# RasPi-BplusHAT_CamSlot.net
KiCad netlist of a schematic drawn in EAGLE
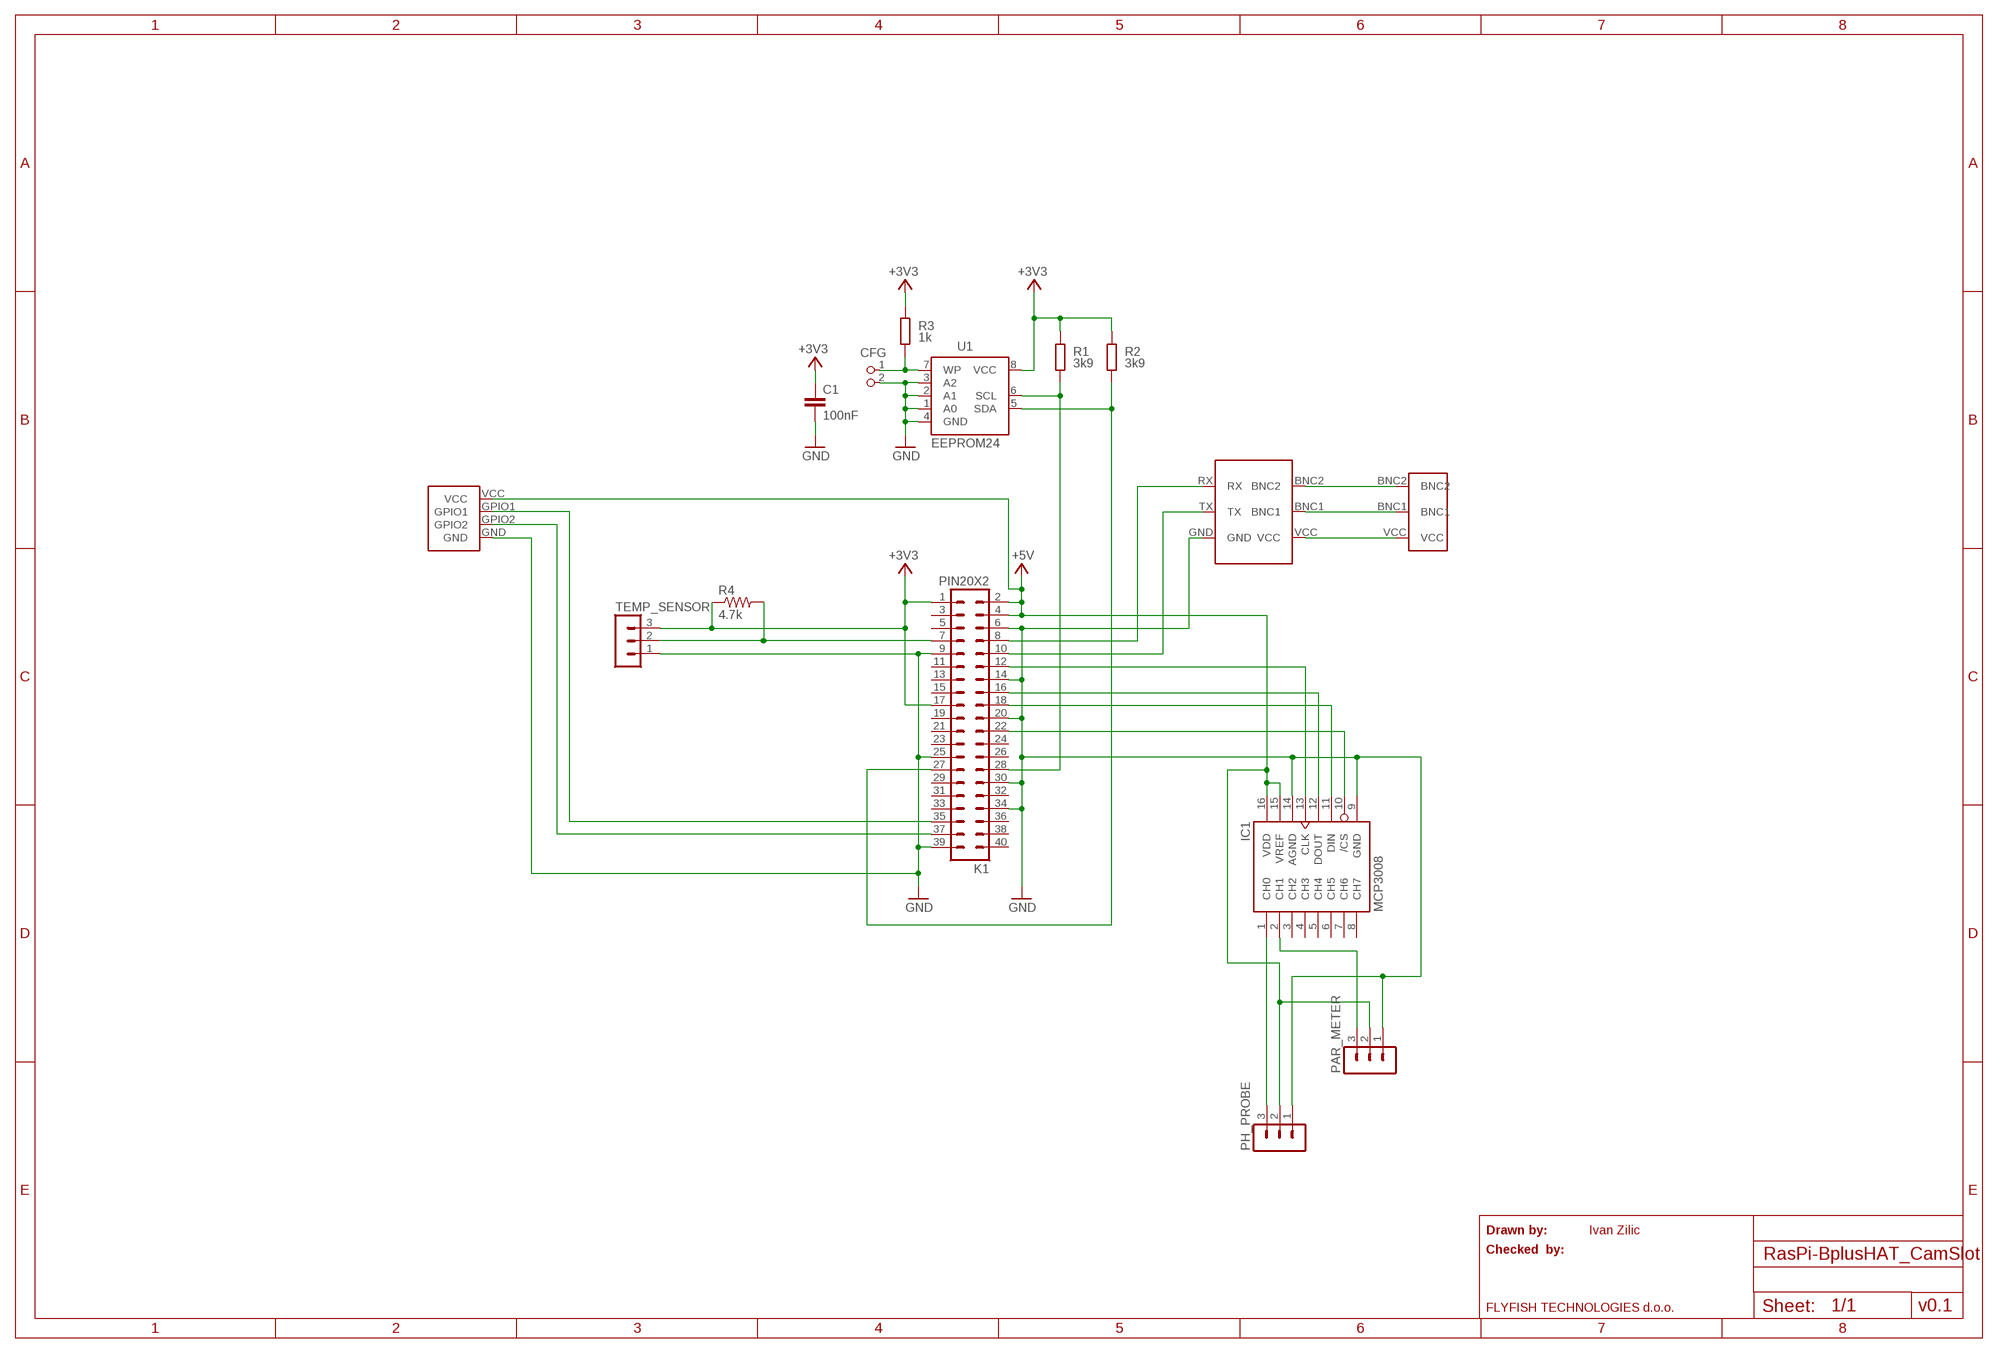
[diagram p0: schematic, sheet 1]

(export (version "E")
  (design (tool "Eeschema 10.0.6"))
  (components
    (comp (ref "C1")
      (value "100nF")
      (footprint "eagle-import:C0805K")
      (libsource (lib "eagle-import") (part "C-EUC0805K"))
    )
    (comp (ref "CFG")
      (value "PIN2_100")
      (footprint "eagle-import:PIN_W_2")
      (libsource (lib "eagle-import") (part "PIN2_100"))
    )
    (comp (ref "IC1")
      (value "MCP3008")
      (footprint "eagle-import:DIL16")
      (libsource (lib "eagle-import") (part "MCP3008"))
    )
    (comp (ref "K1")
      (value "PIN20X2")
      (footprint "eagle-import:PIN_20X2")
      (libsource (lib "eagle-import") (part "PIN20X2"))
    )
    (comp (ref "PAR_METER")
      (value "MA03-1")
      (footprint "eagle-import:MA03-1")
      (libsource (lib "eagle-import") (part "MA03-1"))
    )
    (comp (ref "PH_PROBE")
      (value "MA03-1")
      (footprint "eagle-import:MA03-1")
      (libsource (lib "eagle-import") (part "MA03-1"))
    )
    (comp (ref "R1")
      (value "3k9")
      (footprint "eagle-import:M0805")
      (fields (field (name "TOLERANCE") "5%"))
      (libsource (lib "eagle-import") (part "R-EU_M0805"))
    )
    (comp (ref "R2")
      (value "3k9")
      (footprint "eagle-import:M0805")
      (fields (field (name "TOLERANCE") "5%"))
      (libsource (lib "eagle-import") (part "R-EU_M0805"))
    )
    (comp (ref "R3")
      (value "1k")
      (footprint "eagle-import:M0805")
      (fields (field (name "TOLERANCE") "5%"))
      (libsource (lib "eagle-import") (part "R-EU_M0805"))
    )
    (comp (ref "R4")
      (value "4.7k")
      (footprint "eagle-import:R0805")
      (libsource (lib "eagle-import") (part "R-US_R0805"))
    )
    (comp (ref "TEMP_SENSOR")
      (value "MA03-1")
      (footprint "eagle-import:MA03-1")
      (libsource (lib "eagle-import") (part "MA03-1"))
    )
    (comp (ref "U$1")
      (value "MTA-156")
      (footprint "eagle-import:MTA-156_HEADER")
      (libsource (lib "eagle-import") (part "MTA-156"))
    )
    (comp (ref "U$2")
      (value "ATLAS_EC_CIRCUIT")
      (footprint "eagle-import:ATLAS_EC_CIRCUIT")
      (libsource (lib "eagle-import") (part "ATLAS_EC_CIRCUIT"))
    )
    (comp (ref "U$3")
      (value "ATLAS_EC_PROBE")
      (footprint "eagle-import:ATLAS_EC_PROBE")
      (libsource (lib "eagle-import") (part "ATLAS_EC_PROBE"))
    )
    (comp (ref "U1")
      (value "EEPROM24")
      (footprint "eagle-import:SOIC8")
      (libsource (lib "eagle-import") (part "EEPROM24"))
    )
  )
  (nets
    (net (code "1") (name "+3V3") (class "Default")
      (node (ref "C1") (pin "1") (pinfunction "1_1") (pintype "passive"))
      (node (ref "K1") (pin "1") (pinfunction "1_1") (pintype "passive"))
      (node (ref "K1") (pin "17") (pinfunction "17_17") (pintype "passive"))
      (node (ref "R1") (pin "2") (pinfunction "2_2") (pintype "passive"))
      (node (ref "R2") (pin "2") (pinfunction "2_2") (pintype "passive"))
      (node (ref "R3") (pin "2") (pinfunction "2_2") (pintype "passive"))
      (node (ref "R4") (pin "1") (pinfunction "1_1") (pintype "passive"))
      (node (ref "TEMP_SENSOR") (pin "3") (pinfunction "3_3") (pintype "passive"))
      (node (ref "U1") (pin "8") (pinfunction "VCC_8") (pintype "power_in"))
    )
    (net (code "2") (name "+5V") (class "Default")
      (node (ref "IC1") (pin "15") (pinfunction "VREF_15") (pintype "input"))
      (node (ref "IC1") (pin "16") (pinfunction "VDD_16") (pintype "power_in"))
      (node (ref "K1") (pin "2") (pinfunction "2_2") (pintype "passive"))
      (node (ref "K1") (pin "4") (pinfunction "4_4") (pintype "passive"))
      (node (ref "PAR_METER") (pin "2") (pinfunction "2_2") (pintype "passive"))
      (node (ref "PH_PROBE") (pin "2") (pinfunction "2_2") (pintype "passive"))
      (node (ref "U$1") (pin "VCC") (pinfunction "VCC_VCC") (pintype "power_in"))
    )
    (net (code "3") (name "GND") (class "Default")
      (node (ref "C1") (pin "2") (pinfunction "2_2") (pintype "passive"))
      (node (ref "CFG") (pin "2") (pinfunction "2_2") (pintype "passive"))
      (node (ref "IC1") (pin "14") (pinfunction "AGND_14") (pintype "power_in"))
      (node (ref "IC1") (pin "9") (pinfunction "GND_9") (pintype "power_in"))
      (node (ref "K1") (pin "14") (pinfunction "14_14") (pintype "passive"))
      (node (ref "K1") (pin "20") (pinfunction "20_20") (pintype "passive"))
      (node (ref "K1") (pin "25") (pinfunction "25_25") (pintype "passive"))
      (node (ref "K1") (pin "30") (pinfunction "30_30") (pintype "passive"))
      (node (ref "K1") (pin "34") (pinfunction "34_34") (pintype "passive"))
      (node (ref "K1") (pin "39") (pinfunction "39_39") (pintype "passive"))
      (node (ref "K1") (pin "6") (pinfunction "6_6") (pintype "passive"))
      (node (ref "K1") (pin "9") (pinfunction "9_9") (pintype "passive"))
      (node (ref "PAR_METER") (pin "1") (pinfunction "1_1") (pintype "passive"))
      (node (ref "PH_PROBE") (pin "1") (pinfunction "1_1") (pintype "passive"))
      (node (ref "TEMP_SENSOR") (pin "1") (pinfunction "1_1") (pintype "passive"))
      (node (ref "U$1") (pin "GND") (pinfunction "GND_GND") (pintype "power_in"))
      (node (ref "U$2") (pin "GND") (pinfunction "GND_GND") (pintype "power_in"))
      (node (ref "U1") (pin "1") (pinfunction "A0_1") (pintype "input"))
      (node (ref "U1") (pin "2") (pinfunction "A1_2") (pintype "input"))
      (node (ref "U1") (pin "3") (pinfunction "A2_3") (pintype "input"))
      (node (ref "U1") (pin "4") (pinfunction "GND_4") (pintype "power_in"))
    )
    (net (code "4") (name "Net-(IC1-CH0)") (class "Default")
      (node (ref "IC1") (pin "1") (pinfunction "CH0_1") (pintype "input"))
      (node (ref "PH_PROBE") (pin "3") (pinfunction "3_3") (pintype "passive"))
    )
    (net (code "5") (name "Net-(IC1-CH1)") (class "Default")
      (node (ref "IC1") (pin "2") (pinfunction "CH1_2") (pintype "input"))
      (node (ref "PAR_METER") (pin "3") (pinfunction "3_3") (pintype "passive"))
    )
    (net (code "6") (name "Net-(IC1-CLK)") (class "Default")
      (node (ref "IC1") (pin "13") (pinfunction "CLK_13") (pintype "input"))
      (node (ref "K1") (pin "12") (pinfunction "12_12") (pintype "passive"))
    )
    (net (code "7") (name "Net-(IC1-DIN)") (class "Default")
      (node (ref "IC1") (pin "11") (pinfunction "DIN_11") (pintype "input"))
      (node (ref "K1") (pin "18") (pinfunction "18_18") (pintype "passive"))
    )
    (net (code "8") (name "Net-(IC1-DOUT)") (class "Default")
      (node (ref "IC1") (pin "12") (pinfunction "DOUT_12") (pintype "output"))
      (node (ref "K1") (pin "16") (pinfunction "16_16") (pintype "passive"))
    )
    (net (code "9") (name "Net-(IC1-{slash}CS)") (class "Default")
      (node (ref "IC1") (pin "10") (pinfunction "/CS_10") (pintype "input"))
      (node (ref "K1") (pin "22") (pinfunction "22_22") (pintype "passive"))
    )
    (net (code "10") (name "Net-(K1-Pad7)") (class "Default")
      (node (ref "K1") (pin "7") (pinfunction "7_7") (pintype "passive"))
      (node (ref "R4") (pin "2") (pinfunction "2_2") (pintype "passive"))
      (node (ref "TEMP_SENSOR") (pin "2") (pinfunction "2_2") (pintype "passive"))
    )
    (net (code "11") (name "Net-(K1-Pad8)") (class "Default")
      (node (ref "K1") (pin "8") (pinfunction "8_8") (pintype "passive"))
      (node (ref "U$2") (pin "RX") (pinfunction "RX_RX") (pintype "bidirectional"))
    )
    (net (code "12") (name "Net-(K1-Pad10)") (class "Default")
      (node (ref "K1") (pin "10") (pinfunction "10_10") (pintype "passive"))
      (node (ref "U$2") (pin "TX") (pinfunction "TX_TX") (pintype "bidirectional"))
    )
    (net (code "13") (name "Net-(K1-Pad35)") (class "Default")
      (node (ref "K1") (pin "35") (pinfunction "35_35") (pintype "passive"))
      (node (ref "U$1") (pin "GPIO1") (pinfunction "GPIO1_GPIO1") (pintype "bidirectional"))
    )
    (net (code "14") (name "Net-(K1-Pad37)") (class "Default")
      (node (ref "K1") (pin "37") (pinfunction "37_37") (pintype "passive"))
      (node (ref "U$1") (pin "GPIO2") (pinfunction "GPIO2_GPIO2") (pintype "bidirectional"))
    )
    (net (code "15") (name "Net-(U$2-PadBNC1)") (class "Default")
      (node (ref "U$2") (pin "BNC1") (pinfunction "BNC1_BNC1") (pintype "bidirectional"))
      (node (ref "U$3") (pin "BNC1") (pinfunction "BNC1_BNC1") (pintype "bidirectional"))
    )
    (net (code "16") (name "Net-(U$2-PadBNC2)") (class "Default")
      (node (ref "U$2") (pin "BNC2") (pinfunction "BNC2_BNC2") (pintype "bidirectional"))
      (node (ref "U$3") (pin "BNC2") (pinfunction "BNC2_BNC2") (pintype "bidirectional"))
    )
    (net (code "17") (name "Net-(U$2-PadVCC)") (class "Default")
      (node (ref "U$2") (pin "VCC") (pinfunction "VCC_VCC") (pintype "power_in"))
      (node (ref "U$3") (pin "VCC") (pinfunction "VCC_VCC") (pintype "power_in"))
    )
    (net (code "18") (name "Net-(U1-SCL)") (class "Default")
      (node (ref "K1") (pin "28") (pinfunction "28_28") (pintype "passive"))
      (node (ref "R1") (pin "1") (pinfunction "1_1") (pintype "passive"))
      (node (ref "U1") (pin "6") (pinfunction "SCL_6") (pintype "input"))
    )
    (net (code "19") (name "Net-(U1-SDA)") (class "Default")
      (node (ref "K1") (pin "27") (pinfunction "27_27") (pintype "passive"))
      (node (ref "R2") (pin "1") (pinfunction "1_1") (pintype "passive"))
      (node (ref "U1") (pin "5") (pinfunction "SDA_5") (pintype "bidirectional"))
    )
    (net (code "20") (name "Net-(U1-WP)") (class "Default")
      (node (ref "CFG") (pin "1") (pinfunction "1_1") (pintype "passive"))
      (node (ref "R3") (pin "1") (pinfunction "1_1") (pintype "passive"))
      (node (ref "U1") (pin "7") (pinfunction "WP_7") (pintype "input"))
    )
    (net (code "21") (name "unconnected-(IC1-CH2-Pad3)") (class "Default")
      (node (ref "IC1") (pin "3") (pinfunction "CH2_3") (pintype "input"))
    )
    (net (code "22") (name "unconnected-(IC1-CH3-Pad4)") (class "Default")
      (node (ref "IC1") (pin "4") (pinfunction "CH3_4") (pintype "input"))
    )
    (net (code "23") (name "unconnected-(IC1-CH4-Pad5)") (class "Default")
      (node (ref "IC1") (pin "5") (pinfunction "CH4_5") (pintype "input"))
    )
    (net (code "24") (name "unconnected-(IC1-CH5-Pad6)") (class "Default")
      (node (ref "IC1") (pin "6") (pinfunction "CH5_6") (pintype "input"))
    )
    (net (code "25") (name "unconnected-(IC1-CH6-Pad7)") (class "Default")
      (node (ref "IC1") (pin "7") (pinfunction "CH6_7") (pintype "input"))
    )
    (net (code "26") (name "unconnected-(IC1-CH7-Pad8)") (class "Default")
      (node (ref "IC1") (pin "8") (pinfunction "CH7_8") (pintype "input"))
    )
    (net (code "27") (name "unconnected-(K1-Pad3)") (class "Default")
      (node (ref "K1") (pin "3") (pinfunction "3_3") (pintype "passive"))
    )
    (net (code "28") (name "unconnected-(K1-Pad5)") (class "Default")
      (node (ref "K1") (pin "5") (pinfunction "5_5") (pintype "passive"))
    )
    (net (code "29") (name "unconnected-(K1-Pad11)") (class "Default")
      (node (ref "K1") (pin "11") (pinfunction "11_11") (pintype "passive"))
    )
    (net (code "30") (name "unconnected-(K1-Pad13)") (class "Default")
      (node (ref "K1") (pin "13") (pinfunction "13_13") (pintype "passive"))
    )
    (net (code "31") (name "unconnected-(K1-Pad15)") (class "Default")
      (node (ref "K1") (pin "15") (pinfunction "15_15") (pintype "passive"))
    )
    (net (code "32") (name "unconnected-(K1-Pad19)") (class "Default")
      (node (ref "K1") (pin "19") (pinfunction "19_19") (pintype "passive"))
    )
    (net (code "33") (name "unconnected-(K1-Pad21)") (class "Default")
      (node (ref "K1") (pin "21") (pinfunction "21_21") (pintype "passive"))
    )
    (net (code "34") (name "unconnected-(K1-Pad23)") (class "Default")
      (node (ref "K1") (pin "23") (pinfunction "23_23") (pintype "passive"))
    )
    (net (code "35") (name "unconnected-(K1-Pad24)") (class "Default")
      (node (ref "K1") (pin "24") (pinfunction "24_24") (pintype "passive"))
    )
    (net (code "36") (name "unconnected-(K1-Pad26)") (class "Default")
      (node (ref "K1") (pin "26") (pinfunction "26_26") (pintype "passive"))
    )
    (net (code "37") (name "unconnected-(K1-Pad29)") (class "Default")
      (node (ref "K1") (pin "29") (pinfunction "29_29") (pintype "passive"))
    )
    (net (code "38") (name "unconnected-(K1-Pad31)") (class "Default")
      (node (ref "K1") (pin "31") (pinfunction "31_31") (pintype "passive"))
    )
    (net (code "39") (name "unconnected-(K1-Pad32)") (class "Default")
      (node (ref "K1") (pin "32") (pinfunction "32_32") (pintype "passive"))
    )
    (net (code "40") (name "unconnected-(K1-Pad33)") (class "Default")
      (node (ref "K1") (pin "33") (pinfunction "33_33") (pintype "passive"))
    )
    (net (code "41") (name "unconnected-(K1-Pad36)") (class "Default")
      (node (ref "K1") (pin "36") (pinfunction "36_36") (pintype "passive"))
    )
    (net (code "42") (name "unconnected-(K1-Pad38)") (class "Default")
      (node (ref "K1") (pin "38") (pinfunction "38_38") (pintype "passive"))
    )
    (net (code "43") (name "unconnected-(K1-Pad40)") (class "Default")
      (node (ref "K1") (pin "40") (pinfunction "40_40") (pintype "passive"))
    )
  )
)
